# LEDMatrixi.net
KiCad netlist of a schematic drawn in EAGLE
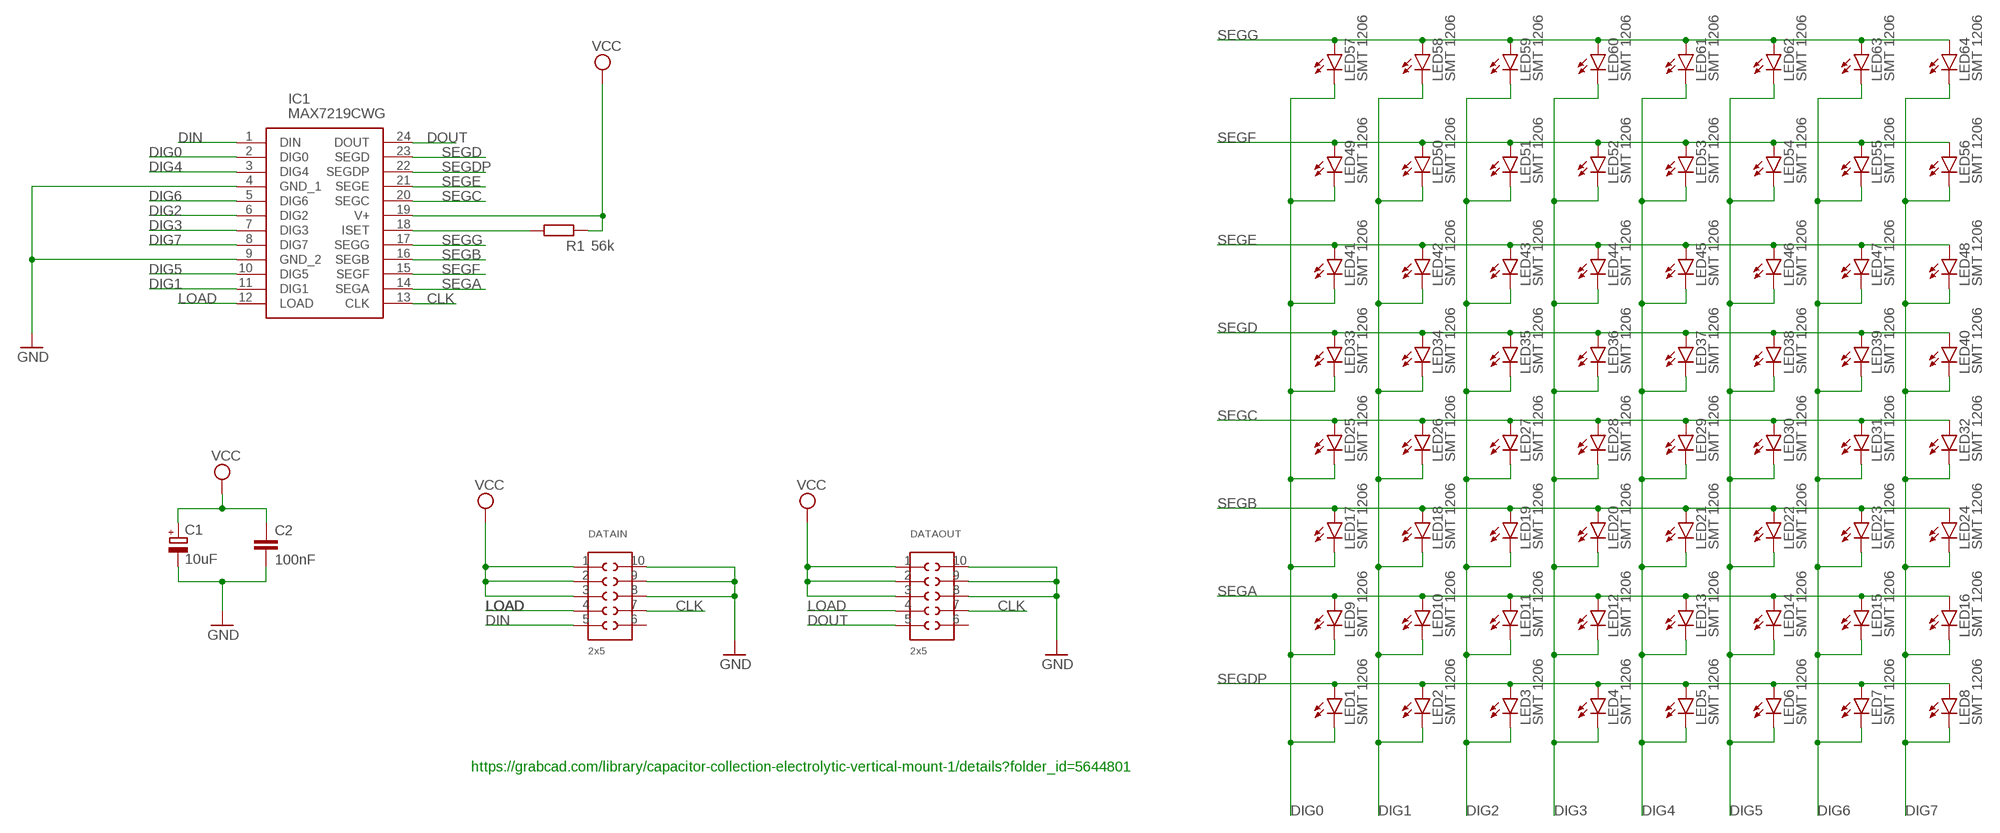
[diagram p0: schematic, sheet 1]

(export (version "E")
  (design (tool "Eeschema 10.0.6"))
  (components
    (comp (ref "C1")
      (value "10uF")
      (footprint "eagle-import:E5-8,5")
      (libsource (lib "eagle-import") (part "CPOL-EUE5-8.5"))
    )
    (comp (ref "C2")
      (value "100nF")
      (footprint "eagle-import:C1206")
      (libsource (lib "eagle-import") (part "C-EUC1206"))
    )
    (comp (ref "DATAIN")
      (value "2x5")
      (footprint "eagle-import:610X1021121")
      (libsource (lib "eagle-import") (part "610X1021121"))
    )
    (comp (ref "DATAOUT")
      (value "2x5")
      (footprint "eagle-import:610X1021121")
      (libsource (lib "eagle-import") (part "610X1021121"))
    )
    (comp (ref "IC1")
      (value "MAX7219CWG")
      (footprint "eagle-import:SOIC127P1032X265-24N")
      (libsource (lib "eagle-import") (part "MAX7219CWG"))
    )
    (comp (ref "LED1")
      (value "SMT 1206")
      (footprint "eagle-import:CHIPLED_1206")
      (libsource (lib "eagle-import") (part "LEDCHIPLED_1206"))
    )
    (comp (ref "LED2")
      (value "SMT 1206")
      (footprint "eagle-import:CHIPLED_1206")
      (libsource (lib "eagle-import") (part "LEDCHIPLED_1206"))
    )
    (comp (ref "LED3")
      (value "SMT 1206")
      (footprint "eagle-import:CHIPLED_1206")
      (libsource (lib "eagle-import") (part "LEDCHIPLED_1206"))
    )
    (comp (ref "LED4")
      (value "SMT 1206")
      (footprint "eagle-import:CHIPLED_1206")
      (libsource (lib "eagle-import") (part "LEDCHIPLED_1206"))
    )
    (comp (ref "LED5")
      (value "SMT 1206")
      (footprint "eagle-import:CHIPLED_1206")
      (libsource (lib "eagle-import") (part "LEDCHIPLED_1206"))
    )
    (comp (ref "LED6")
      (value "SMT 1206")
      (footprint "eagle-import:CHIPLED_1206")
      (libsource (lib "eagle-import") (part "LEDCHIPLED_1206"))
    )
    (comp (ref "LED7")
      (value "SMT 1206")
      (footprint "eagle-import:CHIPLED_1206")
      (libsource (lib "eagle-import") (part "LEDCHIPLED_1206"))
    )
    (comp (ref "LED8")
      (value "SMT 1206")
      (footprint "eagle-import:CHIPLED_1206")
      (libsource (lib "eagle-import") (part "LEDCHIPLED_1206"))
    )
    (comp (ref "LED9")
      (value "SMT 1206")
      (footprint "eagle-import:CHIPLED_1206")
      (libsource (lib "eagle-import") (part "LEDCHIPLED_1206"))
    )
    (comp (ref "LED10")
      (value "SMT 1206")
      (footprint "eagle-import:CHIPLED_1206")
      (libsource (lib "eagle-import") (part "LEDCHIPLED_1206"))
    )
    (comp (ref "LED11")
      (value "SMT 1206")
      (footprint "eagle-import:CHIPLED_1206")
      (libsource (lib "eagle-import") (part "LEDCHIPLED_1206"))
    )
    (comp (ref "LED12")
      (value "SMT 1206")
      (footprint "eagle-import:CHIPLED_1206")
      (libsource (lib "eagle-import") (part "LEDCHIPLED_1206"))
    )
    (comp (ref "LED13")
      (value "SMT 1206")
      (footprint "eagle-import:CHIPLED_1206")
      (libsource (lib "eagle-import") (part "LEDCHIPLED_1206"))
    )
    (comp (ref "LED14")
      (value "SMT 1206")
      (footprint "eagle-import:CHIPLED_1206")
      (libsource (lib "eagle-import") (part "LEDCHIPLED_1206"))
    )
    (comp (ref "LED15")
      (value "SMT 1206")
      (footprint "eagle-import:CHIPLED_1206")
      (libsource (lib "eagle-import") (part "LEDCHIPLED_1206"))
    )
    (comp (ref "LED16")
      (value "SMT 1206")
      (footprint "eagle-import:CHIPLED_1206")
      (libsource (lib "eagle-import") (part "LEDCHIPLED_1206"))
    )
    (comp (ref "LED17")
      (value "SMT 1206")
      (footprint "eagle-import:CHIPLED_1206")
      (libsource (lib "eagle-import") (part "LEDCHIPLED_1206"))
    )
    (comp (ref "LED18")
      (value "SMT 1206")
      (footprint "eagle-import:CHIPLED_1206")
      (libsource (lib "eagle-import") (part "LEDCHIPLED_1206"))
    )
    (comp (ref "LED19")
      (value "SMT 1206")
      (footprint "eagle-import:CHIPLED_1206")
      (libsource (lib "eagle-import") (part "LEDCHIPLED_1206"))
    )
    (comp (ref "LED20")
      (value "SMT 1206")
      (footprint "eagle-import:CHIPLED_1206")
      (libsource (lib "eagle-import") (part "LEDCHIPLED_1206"))
    )
    (comp (ref "LED21")
      (value "SMT 1206")
      (footprint "eagle-import:CHIPLED_1206")
      (libsource (lib "eagle-import") (part "LEDCHIPLED_1206"))
    )
    (comp (ref "LED22")
      (value "SMT 1206")
      (footprint "eagle-import:CHIPLED_1206")
      (libsource (lib "eagle-import") (part "LEDCHIPLED_1206"))
    )
    (comp (ref "LED23")
      (value "SMT 1206")
      (footprint "eagle-import:CHIPLED_1206")
      (libsource (lib "eagle-import") (part "LEDCHIPLED_1206"))
    )
    (comp (ref "LED24")
      (value "SMT 1206")
      (footprint "eagle-import:CHIPLED_1206")
      (libsource (lib "eagle-import") (part "LEDCHIPLED_1206"))
    )
    (comp (ref "LED25")
      (value "SMT 1206")
      (footprint "eagle-import:CHIPLED_1206")
      (libsource (lib "eagle-import") (part "LEDCHIPLED_1206"))
    )
    (comp (ref "LED26")
      (value "SMT 1206")
      (footprint "eagle-import:CHIPLED_1206")
      (libsource (lib "eagle-import") (part "LEDCHIPLED_1206"))
    )
    (comp (ref "LED27")
      (value "SMT 1206")
      (footprint "eagle-import:CHIPLED_1206")
      (libsource (lib "eagle-import") (part "LEDCHIPLED_1206"))
    )
    (comp (ref "LED28")
      (value "SMT 1206")
      (footprint "eagle-import:CHIPLED_1206")
      (libsource (lib "eagle-import") (part "LEDCHIPLED_1206"))
    )
    (comp (ref "LED29")
      (value "SMT 1206")
      (footprint "eagle-import:CHIPLED_1206")
      (libsource (lib "eagle-import") (part "LEDCHIPLED_1206"))
    )
    (comp (ref "LED30")
      (value "SMT 1206")
      (footprint "eagle-import:CHIPLED_1206")
      (libsource (lib "eagle-import") (part "LEDCHIPLED_1206"))
    )
    (comp (ref "LED31")
      (value "SMT 1206")
      (footprint "eagle-import:CHIPLED_1206")
      (libsource (lib "eagle-import") (part "LEDCHIPLED_1206"))
    )
    (comp (ref "LED32")
      (value "SMT 1206")
      (footprint "eagle-import:CHIPLED_1206")
      (libsource (lib "eagle-import") (part "LEDCHIPLED_1206"))
    )
    (comp (ref "LED33")
      (value "SMT 1206")
      (footprint "eagle-import:CHIPLED_1206")
      (libsource (lib "eagle-import") (part "LEDCHIPLED_1206"))
    )
    (comp (ref "LED34")
      (value "SMT 1206")
      (footprint "eagle-import:CHIPLED_1206")
      (libsource (lib "eagle-import") (part "LEDCHIPLED_1206"))
    )
    (comp (ref "LED35")
      (value "SMT 1206")
      (footprint "eagle-import:CHIPLED_1206")
      (libsource (lib "eagle-import") (part "LEDCHIPLED_1206"))
    )
    (comp (ref "LED36")
      (value "SMT 1206")
      (footprint "eagle-import:CHIPLED_1206")
      (libsource (lib "eagle-import") (part "LEDCHIPLED_1206"))
    )
    (comp (ref "LED37")
      (value "SMT 1206")
      (footprint "eagle-import:CHIPLED_1206")
      (libsource (lib "eagle-import") (part "LEDCHIPLED_1206"))
    )
    (comp (ref "LED38")
      (value "SMT 1206")
      (footprint "eagle-import:CHIPLED_1206")
      (libsource (lib "eagle-import") (part "LEDCHIPLED_1206"))
    )
    (comp (ref "LED39")
      (value "SMT 1206")
      (footprint "eagle-import:CHIPLED_1206")
      (libsource (lib "eagle-import") (part "LEDCHIPLED_1206"))
    )
    (comp (ref "LED40")
      (value "SMT 1206")
      (footprint "eagle-import:CHIPLED_1206")
      (libsource (lib "eagle-import") (part "LEDCHIPLED_1206"))
    )
    (comp (ref "LED41")
      (value "SMT 1206")
      (footprint "eagle-import:CHIPLED_1206")
      (libsource (lib "eagle-import") (part "LEDCHIPLED_1206"))
    )
    (comp (ref "LED42")
      (value "SMT 1206")
      (footprint "eagle-import:CHIPLED_1206")
      (libsource (lib "eagle-import") (part "LEDCHIPLED_1206"))
    )
    (comp (ref "LED43")
      (value "SMT 1206")
      (footprint "eagle-import:CHIPLED_1206")
      (libsource (lib "eagle-import") (part "LEDCHIPLED_1206"))
    )
    (comp (ref "LED44")
      (value "SMT 1206")
      (footprint "eagle-import:CHIPLED_1206")
      (libsource (lib "eagle-import") (part "LEDCHIPLED_1206"))
    )
    (comp (ref "LED45")
      (value "SMT 1206")
      (footprint "eagle-import:CHIPLED_1206")
      (libsource (lib "eagle-import") (part "LEDCHIPLED_1206"))
    )
    (comp (ref "LED46")
      (value "SMT 1206")
      (footprint "eagle-import:CHIPLED_1206")
      (libsource (lib "eagle-import") (part "LEDCHIPLED_1206"))
    )
    (comp (ref "LED47")
      (value "SMT 1206")
      (footprint "eagle-import:CHIPLED_1206")
      (libsource (lib "eagle-import") (part "LEDCHIPLED_1206"))
    )
    (comp (ref "LED48")
      (value "SMT 1206")
      (footprint "eagle-import:CHIPLED_1206")
      (libsource (lib "eagle-import") (part "LEDCHIPLED_1206"))
    )
    (comp (ref "LED49")
      (value "SMT 1206")
      (footprint "eagle-import:CHIPLED_1206")
      (libsource (lib "eagle-import") (part "LEDCHIPLED_1206"))
    )
    (comp (ref "LED50")
      (value "SMT 1206")
      (footprint "eagle-import:CHIPLED_1206")
      (libsource (lib "eagle-import") (part "LEDCHIPLED_1206"))
    )
    (comp (ref "LED51")
      (value "SMT 1206")
      (footprint "eagle-import:CHIPLED_1206")
      (libsource (lib "eagle-import") (part "LEDCHIPLED_1206"))
    )
    (comp (ref "LED52")
      (value "SMT 1206")
      (footprint "eagle-import:CHIPLED_1206")
      (libsource (lib "eagle-import") (part "LEDCHIPLED_1206"))
    )
    (comp (ref "LED53")
      (value "SMT 1206")
      (footprint "eagle-import:CHIPLED_1206")
      (libsource (lib "eagle-import") (part "LEDCHIPLED_1206"))
    )
    (comp (ref "LED54")
      (value "SMT 1206")
      (footprint "eagle-import:CHIPLED_1206")
      (libsource (lib "eagle-import") (part "LEDCHIPLED_1206"))
    )
    (comp (ref "LED55")
      (value "SMT 1206")
      (footprint "eagle-import:CHIPLED_1206")
      (libsource (lib "eagle-import") (part "LEDCHIPLED_1206"))
    )
    (comp (ref "LED56")
      (value "SMT 1206")
      (footprint "eagle-import:CHIPLED_1206")
      (libsource (lib "eagle-import") (part "LEDCHIPLED_1206"))
    )
    (comp (ref "LED57")
      (value "SMT 1206")
      (footprint "eagle-import:CHIPLED_1206")
      (libsource (lib "eagle-import") (part "LEDCHIPLED_1206"))
    )
    (comp (ref "LED58")
      (value "SMT 1206")
      (footprint "eagle-import:CHIPLED_1206")
      (libsource (lib "eagle-import") (part "LEDCHIPLED_1206"))
    )
    (comp (ref "LED59")
      (value "SMT 1206")
      (footprint "eagle-import:CHIPLED_1206")
      (libsource (lib "eagle-import") (part "LEDCHIPLED_1206"))
    )
    (comp (ref "LED60")
      (value "SMT 1206")
      (footprint "eagle-import:CHIPLED_1206")
      (libsource (lib "eagle-import") (part "LEDCHIPLED_1206"))
    )
    (comp (ref "LED61")
      (value "SMT 1206")
      (footprint "eagle-import:CHIPLED_1206")
      (libsource (lib "eagle-import") (part "LEDCHIPLED_1206"))
    )
    (comp (ref "LED62")
      (value "SMT 1206")
      (footprint "eagle-import:CHIPLED_1206")
      (libsource (lib "eagle-import") (part "LEDCHIPLED_1206"))
    )
    (comp (ref "LED63")
      (value "SMT 1206")
      (footprint "eagle-import:CHIPLED_1206")
      (libsource (lib "eagle-import") (part "LEDCHIPLED_1206"))
    )
    (comp (ref "LED64")
      (value "SMT 1206")
      (footprint "eagle-import:CHIPLED_1206")
      (libsource (lib "eagle-import") (part "LEDCHIPLED_1206"))
    )
    (comp (ref "R1")
      (value "56k")
      (footprint "eagle-import:R1206")
      (libsource (lib "eagle-import") (part "R-EU_R1206"))
    )
  )
  (nets
    (net (code "1") (name "/CLK") (class "Default")
      (node (ref "DATAIN") (pin "7") (pinfunction "7_7") (pintype "passive"))
      (node (ref "DATAOUT") (pin "7") (pinfunction "7_7") (pintype "passive"))
      (node (ref "IC1") (pin "13") (pinfunction "CLK_13") (pintype "bidirectional"))
    )
    (net (code "2") (name "/DIG0") (class "Default")
      (node (ref "IC1") (pin "2") (pinfunction "DIG0_2") (pintype "bidirectional"))
      (node (ref "LED1") (pin "C") (pinfunction "C_C") (pintype "passive"))
      (node (ref "LED17") (pin "C") (pinfunction "C_C") (pintype "passive"))
      (node (ref "LED25") (pin "C") (pinfunction "C_C") (pintype "passive"))
      (node (ref "LED33") (pin "C") (pinfunction "C_C") (pintype "passive"))
      (node (ref "LED41") (pin "C") (pinfunction "C_C") (pintype "passive"))
      (node (ref "LED49") (pin "C") (pinfunction "C_C") (pintype "passive"))
      (node (ref "LED57") (pin "C") (pinfunction "C_C") (pintype "passive"))
      (node (ref "LED9") (pin "C") (pinfunction "C_C") (pintype "passive"))
    )
    (net (code "3") (name "/DIG1") (class "Default")
      (node (ref "IC1") (pin "11") (pinfunction "DIG1_11") (pintype "bidirectional"))
      (node (ref "LED10") (pin "C") (pinfunction "C_C") (pintype "passive"))
      (node (ref "LED18") (pin "C") (pinfunction "C_C") (pintype "passive"))
      (node (ref "LED2") (pin "C") (pinfunction "C_C") (pintype "passive"))
      (node (ref "LED26") (pin "C") (pinfunction "C_C") (pintype "passive"))
      (node (ref "LED34") (pin "C") (pinfunction "C_C") (pintype "passive"))
      (node (ref "LED42") (pin "C") (pinfunction "C_C") (pintype "passive"))
      (node (ref "LED50") (pin "C") (pinfunction "C_C") (pintype "passive"))
      (node (ref "LED58") (pin "C") (pinfunction "C_C") (pintype "passive"))
    )
    (net (code "4") (name "/DIG2") (class "Default")
      (node (ref "IC1") (pin "6") (pinfunction "DIG2_6") (pintype "bidirectional"))
      (node (ref "LED11") (pin "C") (pinfunction "C_C") (pintype "passive"))
      (node (ref "LED19") (pin "C") (pinfunction "C_C") (pintype "passive"))
      (node (ref "LED27") (pin "C") (pinfunction "C_C") (pintype "passive"))
      (node (ref "LED3") (pin "C") (pinfunction "C_C") (pintype "passive"))
      (node (ref "LED35") (pin "C") (pinfunction "C_C") (pintype "passive"))
      (node (ref "LED43") (pin "C") (pinfunction "C_C") (pintype "passive"))
      (node (ref "LED51") (pin "C") (pinfunction "C_C") (pintype "passive"))
      (node (ref "LED59") (pin "C") (pinfunction "C_C") (pintype "passive"))
    )
    (net (code "5") (name "/DIG3") (class "Default")
      (node (ref "IC1") (pin "7") (pinfunction "DIG3_7") (pintype "bidirectional"))
      (node (ref "LED12") (pin "C") (pinfunction "C_C") (pintype "passive"))
      (node (ref "LED20") (pin "C") (pinfunction "C_C") (pintype "passive"))
      (node (ref "LED28") (pin "C") (pinfunction "C_C") (pintype "passive"))
      (node (ref "LED36") (pin "C") (pinfunction "C_C") (pintype "passive"))
      (node (ref "LED4") (pin "C") (pinfunction "C_C") (pintype "passive"))
      (node (ref "LED44") (pin "C") (pinfunction "C_C") (pintype "passive"))
      (node (ref "LED52") (pin "C") (pinfunction "C_C") (pintype "passive"))
      (node (ref "LED60") (pin "C") (pinfunction "C_C") (pintype "passive"))
    )
    (net (code "6") (name "/DIG4") (class "Default")
      (node (ref "IC1") (pin "3") (pinfunction "DIG4_3") (pintype "bidirectional"))
      (node (ref "LED13") (pin "C") (pinfunction "C_C") (pintype "passive"))
      (node (ref "LED21") (pin "C") (pinfunction "C_C") (pintype "passive"))
      (node (ref "LED29") (pin "C") (pinfunction "C_C") (pintype "passive"))
      (node (ref "LED37") (pin "C") (pinfunction "C_C") (pintype "passive"))
      (node (ref "LED45") (pin "C") (pinfunction "C_C") (pintype "passive"))
      (node (ref "LED5") (pin "C") (pinfunction "C_C") (pintype "passive"))
      (node (ref "LED53") (pin "C") (pinfunction "C_C") (pintype "passive"))
      (node (ref "LED61") (pin "C") (pinfunction "C_C") (pintype "passive"))
    )
    (net (code "7") (name "/DIG5") (class "Default")
      (node (ref "IC1") (pin "10") (pinfunction "DIG5_10") (pintype "bidirectional"))
      (node (ref "LED14") (pin "C") (pinfunction "C_C") (pintype "passive"))
      (node (ref "LED22") (pin "C") (pinfunction "C_C") (pintype "passive"))
      (node (ref "LED30") (pin "C") (pinfunction "C_C") (pintype "passive"))
      (node (ref "LED38") (pin "C") (pinfunction "C_C") (pintype "passive"))
      (node (ref "LED46") (pin "C") (pinfunction "C_C") (pintype "passive"))
      (node (ref "LED54") (pin "C") (pinfunction "C_C") (pintype "passive"))
      (node (ref "LED6") (pin "C") (pinfunction "C_C") (pintype "passive"))
      (node (ref "LED62") (pin "C") (pinfunction "C_C") (pintype "passive"))
    )
    (net (code "8") (name "/DIG6") (class "Default")
      (node (ref "IC1") (pin "5") (pinfunction "DIG6_5") (pintype "bidirectional"))
      (node (ref "LED15") (pin "C") (pinfunction "C_C") (pintype "passive"))
      (node (ref "LED23") (pin "C") (pinfunction "C_C") (pintype "passive"))
      (node (ref "LED31") (pin "C") (pinfunction "C_C") (pintype "passive"))
      (node (ref "LED39") (pin "C") (pinfunction "C_C") (pintype "passive"))
      (node (ref "LED47") (pin "C") (pinfunction "C_C") (pintype "passive"))
      (node (ref "LED55") (pin "C") (pinfunction "C_C") (pintype "passive"))
      (node (ref "LED63") (pin "C") (pinfunction "C_C") (pintype "passive"))
      (node (ref "LED7") (pin "C") (pinfunction "C_C") (pintype "passive"))
    )
    (net (code "9") (name "/DIG7") (class "Default")
      (node (ref "IC1") (pin "8") (pinfunction "DIG7_8") (pintype "bidirectional"))
      (node (ref "LED16") (pin "C") (pinfunction "C_C") (pintype "passive"))
      (node (ref "LED24") (pin "C") (pinfunction "C_C") (pintype "passive"))
      (node (ref "LED32") (pin "C") (pinfunction "C_C") (pintype "passive"))
      (node (ref "LED40") (pin "C") (pinfunction "C_C") (pintype "passive"))
      (node (ref "LED48") (pin "C") (pinfunction "C_C") (pintype "passive"))
      (node (ref "LED56") (pin "C") (pinfunction "C_C") (pintype "passive"))
      (node (ref "LED64") (pin "C") (pinfunction "C_C") (pintype "passive"))
      (node (ref "LED8") (pin "C") (pinfunction "C_C") (pintype "passive"))
    )
    (net (code "10") (name "/DIN") (class "Default")
      (node (ref "DATAIN") (pin "5") (pinfunction "5_5") (pintype "passive"))
      (node (ref "IC1") (pin "1") (pinfunction "DIN_1") (pintype "bidirectional"))
    )
    (net (code "11") (name "/DOUT") (class "Default")
      (node (ref "DATAOUT") (pin "5") (pinfunction "5_5") (pintype "passive"))
      (node (ref "IC1") (pin "24") (pinfunction "DOUT_24") (pintype "bidirectional"))
    )
    (net (code "12") (name "/LOAD") (class "Default")
      (node (ref "DATAIN") (pin "4") (pinfunction "4_4") (pintype "passive"))
      (node (ref "DATAOUT") (pin "4") (pinfunction "4_4") (pintype "passive"))
      (node (ref "IC1") (pin "12") (pinfunction "LOAD_12") (pintype "bidirectional"))
    )
    (net (code "13") (name "/SEGA") (class "Default")
      (node (ref "IC1") (pin "14") (pinfunction "SEGA_14") (pintype "bidirectional"))
      (node (ref "LED10") (pin "A") (pinfunction "A_A") (pintype "passive"))
      (node (ref "LED11") (pin "A") (pinfunction "A_A") (pintype "passive"))
      (node (ref "LED12") (pin "A") (pinfunction "A_A") (pintype "passive"))
      (node (ref "LED13") (pin "A") (pinfunction "A_A") (pintype "passive"))
      (node (ref "LED14") (pin "A") (pinfunction "A_A") (pintype "passive"))
      (node (ref "LED15") (pin "A") (pinfunction "A_A") (pintype "passive"))
      (node (ref "LED16") (pin "A") (pinfunction "A_A") (pintype "passive"))
      (node (ref "LED9") (pin "A") (pinfunction "A_A") (pintype "passive"))
    )
    (net (code "14") (name "/SEGB") (class "Default")
      (node (ref "IC1") (pin "16") (pinfunction "SEGB_16") (pintype "bidirectional"))
      (node (ref "LED17") (pin "A") (pinfunction "A_A") (pintype "passive"))
      (node (ref "LED18") (pin "A") (pinfunction "A_A") (pintype "passive"))
      (node (ref "LED19") (pin "A") (pinfunction "A_A") (pintype "passive"))
      (node (ref "LED20") (pin "A") (pinfunction "A_A") (pintype "passive"))
      (node (ref "LED21") (pin "A") (pinfunction "A_A") (pintype "passive"))
      (node (ref "LED22") (pin "A") (pinfunction "A_A") (pintype "passive"))
      (node (ref "LED23") (pin "A") (pinfunction "A_A") (pintype "passive"))
      (node (ref "LED24") (pin "A") (pinfunction "A_A") (pintype "passive"))
    )
    (net (code "15") (name "/SEGC") (class "Default")
      (node (ref "IC1") (pin "20") (pinfunction "SEGC_20") (pintype "bidirectional"))
      (node (ref "LED25") (pin "A") (pinfunction "A_A") (pintype "passive"))
      (node (ref "LED26") (pin "A") (pinfunction "A_A") (pintype "passive"))
      (node (ref "LED27") (pin "A") (pinfunction "A_A") (pintype "passive"))
      (node (ref "LED28") (pin "A") (pinfunction "A_A") (pintype "passive"))
      (node (ref "LED29") (pin "A") (pinfunction "A_A") (pintype "passive"))
      (node (ref "LED30") (pin "A") (pinfunction "A_A") (pintype "passive"))
      (node (ref "LED31") (pin "A") (pinfunction "A_A") (pintype "passive"))
      (node (ref "LED32") (pin "A") (pinfunction "A_A") (pintype "passive"))
    )
    (net (code "16") (name "/SEGD") (class "Default")
      (node (ref "IC1") (pin "23") (pinfunction "SEGD_23") (pintype "bidirectional"))
      (node (ref "LED33") (pin "A") (pinfunction "A_A") (pintype "passive"))
      (node (ref "LED34") (pin "A") (pinfunction "A_A") (pintype "passive"))
      (node (ref "LED35") (pin "A") (pinfunction "A_A") (pintype "passive"))
      (node (ref "LED36") (pin "A") (pinfunction "A_A") (pintype "passive"))
      (node (ref "LED37") (pin "A") (pinfunction "A_A") (pintype "passive"))
      (node (ref "LED38") (pin "A") (pinfunction "A_A") (pintype "passive"))
      (node (ref "LED39") (pin "A") (pinfunction "A_A") (pintype "passive"))
      (node (ref "LED40") (pin "A") (pinfunction "A_A") (pintype "passive"))
    )
    (net (code "17") (name "/SEGDP") (class "Default")
      (node (ref "IC1") (pin "22") (pinfunction "SEGDP_22") (pintype "bidirectional"))
      (node (ref "LED1") (pin "A") (pinfunction "A_A") (pintype "passive"))
      (node (ref "LED2") (pin "A") (pinfunction "A_A") (pintype "passive"))
      (node (ref "LED3") (pin "A") (pinfunction "A_A") (pintype "passive"))
      (node (ref "LED4") (pin "A") (pinfunction "A_A") (pintype "passive"))
      (node (ref "LED5") (pin "A") (pinfunction "A_A") (pintype "passive"))
      (node (ref "LED6") (pin "A") (pinfunction "A_A") (pintype "passive"))
      (node (ref "LED7") (pin "A") (pinfunction "A_A") (pintype "passive"))
      (node (ref "LED8") (pin "A") (pinfunction "A_A") (pintype "passive"))
    )
    (net (code "18") (name "/SEGE") (class "Default")
      (node (ref "IC1") (pin "21") (pinfunction "SEGE_21") (pintype "bidirectional"))
      (node (ref "LED41") (pin "A") (pinfunction "A_A") (pintype "passive"))
      (node (ref "LED42") (pin "A") (pinfunction "A_A") (pintype "passive"))
      (node (ref "LED43") (pin "A") (pinfunction "A_A") (pintype "passive"))
      (node (ref "LED44") (pin "A") (pinfunction "A_A") (pintype "passive"))
      (node (ref "LED45") (pin "A") (pinfunction "A_A") (pintype "passive"))
      (node (ref "LED46") (pin "A") (pinfunction "A_A") (pintype "passive"))
      (node (ref "LED47") (pin "A") (pinfunction "A_A") (pintype "passive"))
      (node (ref "LED48") (pin "A") (pinfunction "A_A") (pintype "passive"))
    )
    (net (code "19") (name "/SEGF") (class "Default")
      (node (ref "IC1") (pin "15") (pinfunction "SEGF_15") (pintype "bidirectional"))
      (node (ref "LED49") (pin "A") (pinfunction "A_A") (pintype "passive"))
      (node (ref "LED50") (pin "A") (pinfunction "A_A") (pintype "passive"))
      (node (ref "LED51") (pin "A") (pinfunction "A_A") (pintype "passive"))
      (node (ref "LED52") (pin "A") (pinfunction "A_A") (pintype "passive"))
      (node (ref "LED53") (pin "A") (pinfunction "A_A") (pintype "passive"))
      (node (ref "LED54") (pin "A") (pinfunction "A_A") (pintype "passive"))
      (node (ref "LED55") (pin "A") (pinfunction "A_A") (pintype "passive"))
      (node (ref "LED56") (pin "A") (pinfunction "A_A") (pintype "passive"))
    )
    (net (code "20") (name "/SEGG") (class "Default")
      (node (ref "IC1") (pin "17") (pinfunction "SEGG_17") (pintype "bidirectional"))
      (node (ref "LED57") (pin "A") (pinfunction "A_A") (pintype "passive"))
      (node (ref "LED58") (pin "A") (pinfunction "A_A") (pintype "passive"))
      (node (ref "LED59") (pin "A") (pinfunction "A_A") (pintype "passive"))
      (node (ref "LED60") (pin "A") (pinfunction "A_A") (pintype "passive"))
      (node (ref "LED61") (pin "A") (pinfunction "A_A") (pintype "passive"))
      (node (ref "LED62") (pin "A") (pinfunction "A_A") (pintype "passive"))
      (node (ref "LED63") (pin "A") (pinfunction "A_A") (pintype "passive"))
      (node (ref "LED64") (pin "A") (pinfunction "A_A") (pintype "passive"))
    )
    (net (code "21") (name "GND") (class "Default")
      (node (ref "C1") (pin "-") (pinfunction "-_-") (pintype "passive"))
      (node (ref "C2") (pin "2") (pinfunction "2_2") (pintype "passive"))
      (node (ref "DATAIN") (pin "10") (pinfunction "10_10") (pintype "passive"))
      (node (ref "DATAIN") (pin "8") (pinfunction "8_8") (pintype "passive"))
      (node (ref "DATAIN") (pin "9") (pinfunction "9_9") (pintype "passive"))
      (node (ref "DATAOUT") (pin "10") (pinfunction "10_10") (pintype "passive"))
      (node (ref "DATAOUT") (pin "8") (pinfunction "8_8") (pintype "passive"))
      (node (ref "DATAOUT") (pin "9") (pinfunction "9_9") (pintype "passive"))
      (node (ref "IC1") (pin "4") (pinfunction "GND_1_4") (pintype "bidirectional"))
      (node (ref "IC1") (pin "9") (pinfunction "GND_2_9") (pintype "bidirectional"))
    )
    (net (code "22") (name "Net-(IC1-ISET)") (class "Default")
      (node (ref "IC1") (pin "18") (pinfunction "ISET_18") (pintype "bidirectional"))
      (node (ref "R1") (pin "1") (pinfunction "1_1") (pintype "passive"))
    )
    (net (code "23") (name "VCC") (class "Default")
      (node (ref "C1") (pin "+") (pinfunction "+_+") (pintype "passive"))
      (node (ref "C2") (pin "1") (pinfunction "1_1") (pintype "passive"))
      (node (ref "DATAIN") (pin "1") (pinfunction "1_1") (pintype "passive"))
      (node (ref "DATAIN") (pin "2") (pinfunction "2_2") (pintype "passive"))
      (node (ref "DATAIN") (pin "3") (pinfunction "3_3") (pintype "passive"))
      (node (ref "DATAOUT") (pin "1") (pinfunction "1_1") (pintype "passive"))
      (node (ref "DATAOUT") (pin "2") (pinfunction "2_2") (pintype "passive"))
      (node (ref "DATAOUT") (pin "3") (pinfunction "3_3") (pintype "passive"))
      (node (ref "IC1") (pin "19") (pinfunction "V+_19") (pintype "bidirectional"))
      (node (ref "R1") (pin "2") (pinfunction "2_2") (pintype "passive"))
    )
    (net (code "24") (name "unconnected-(DATAIN-Pad6)") (class "Default")
      (node (ref "DATAIN") (pin "6") (pinfunction "6_6") (pintype "passive"))
    )
    (net (code "25") (name "unconnected-(DATAOUT-Pad6)") (class "Default")
      (node (ref "DATAOUT") (pin "6") (pinfunction "6_6") (pintype "passive"))
    )
  )
)
